# playB.net
KiCad netlist of a schematic drawn in Altium Designer
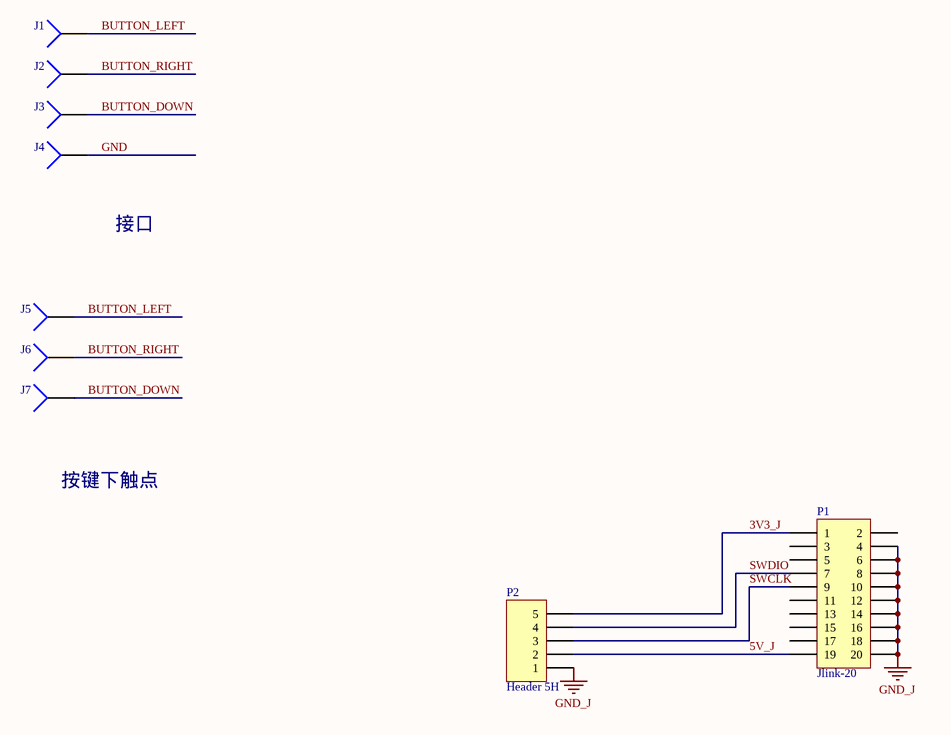
[diagram p0: playB.SchDoc]

(export (version "E")
  (design (tool "Eeschema 10.0.6"))
  (components
    (comp (ref "J1")
      (value "PAD")
      (footprint "LINK_HOLE")
      (description "Socket")
      (fields (field (name "PUBLISHER") "Altium Limited"))
      (libsource (lib "Miscellaneous Connectors") (part "Socket"))
    )
    (comp (ref "J2")
      (value "PAD")
      (footprint "LINK_HOLE")
      (description "Socket")
      (fields (field (name "PUBLISHER") "Altium Limited"))
      (libsource (lib "Miscellaneous Connectors") (part "Socket"))
    )
    (comp (ref "J3")
      (value "PAD")
      (footprint "LINK_HOLE")
      (description "Socket")
      (fields (field (name "PUBLISHER") "Altium Limited"))
      (libsource (lib "Miscellaneous Connectors") (part "Socket"))
    )
    (comp (ref "J4")
      (value "PAD")
      (footprint "LINK_HOLE")
      (description "Socket")
      (fields (field (name "PUBLISHER") "Altium Limited"))
      (libsource (lib "Miscellaneous Connectors") (part "Socket"))
    )
    (comp (ref "J5")
      (value "PAD")
      (footprint "Button_Pad")
      (description "Socket")
      (fields (field (name "PUBLISHER") "Altium Limited"))
      (libsource (lib "Miscellaneous Connectors") (part "Socket"))
    )
    (comp (ref "J6")
      (value "PAD")
      (footprint "Button_Pad")
      (description "Socket")
      (fields (field (name "PUBLISHER") "Altium Limited"))
      (libsource (lib "Miscellaneous Connectors") (part "Socket"))
    )
    (comp (ref "J7")
      (value "PAD")
      (footprint "Button_Pad")
      (description "Socket")
      (fields (field (name "PUBLISHER") "Altium Limited"))
      (libsource (lib "Miscellaneous Connectors") (part "Socket"))
    )
    (comp (ref "P1")
      (value "Jlink-20")
      (footprint "J-LINK")
      (description "Header, 10-Pin, Dual row")
      (fields (field (name "PUBLISHER") "Altium Limited"))
      (libsource (lib "Miscellaneous Connectors") (part "Header 10X2"))
    )
    (comp (ref "P2")
      (value "Header 5H")
      (footprint "connect_5pin")
      (description "Header, 5-Pin, Right Angle")
      (fields (field (name "PUBLISHER") "Altium Limited"))
      (libsource (lib "Miscellaneous Connectors") (part "Header 5H"))
    )
  )
  (nets
    (net (code "1") (name "/3V3_J") (class "Default")
      (node (ref "P1") (pin "1") (pinfunction "1_1") (pintype "passive"))
      (node (ref "P2") (pin "5") (pinfunction "5_5") (pintype "passive"))
    )
    (net (code "2") (name "/5V_J") (class "Default")
      (node (ref "P1") (pin "19") (pinfunction "19_19") (pintype "passive"))
      (node (ref "P2") (pin "2") (pinfunction "2_2") (pintype "passive"))
    )
    (net (code "3") (name "/BUTTON_DOWN") (class "Default")
      (node (ref "J3") (pin "1") (pinfunction "1_1") (pintype "passive"))
      (node (ref "J7") (pin "1") (pinfunction "1_1") (pintype "passive"))
    )
    (net (code "4") (name "/BUTTON_LEFT") (class "Default")
      (node (ref "J1") (pin "1") (pinfunction "1_1") (pintype "passive"))
      (node (ref "J5") (pin "1") (pinfunction "1_1") (pintype "passive"))
    )
    (net (code "5") (name "/BUTTON_RIGHT") (class "Default")
      (node (ref "J2") (pin "1") (pinfunction "1_1") (pintype "passive"))
      (node (ref "J6") (pin "1") (pinfunction "1_1") (pintype "passive"))
    )
    (net (code "6") (name "/GND") (class "Default")
      (node (ref "J4") (pin "1") (pinfunction "1_1") (pintype "passive"))
    )
    (net (code "7") (name "/SWCLK") (class "Default")
      (node (ref "P1") (pin "9") (pinfunction "9_9") (pintype "passive"))
      (node (ref "P2") (pin "3") (pinfunction "3_3") (pintype "passive"))
    )
    (net (code "8") (name "/SWDIO") (class "Default")
      (node (ref "P1") (pin "7") (pinfunction "7_7") (pintype "passive"))
      (node (ref "P2") (pin "4") (pinfunction "4_4") (pintype "passive"))
    )
    (net (code "9") (name "GND_J") (class "Default")
      (node (ref "P1") (pin "10") (pinfunction "10_10") (pintype "passive"))
      (node (ref "P1") (pin "12") (pinfunction "12_12") (pintype "passive"))
      (node (ref "P1") (pin "14") (pinfunction "14_14") (pintype "passive"))
      (node (ref "P1") (pin "16") (pinfunction "16_16") (pintype "passive"))
      (node (ref "P1") (pin "18") (pinfunction "18_18") (pintype "passive"))
      (node (ref "P1") (pin "20") (pinfunction "20_20") (pintype "passive"))
      (node (ref "P1") (pin "4") (pinfunction "4_4") (pintype "passive"))
      (node (ref "P1") (pin "6") (pinfunction "6_6") (pintype "passive"))
      (node (ref "P1") (pin "8") (pinfunction "8_8") (pintype "passive"))
      (node (ref "P2") (pin "1") (pinfunction "1_1") (pintype "passive"))
    )
    (net (code "10") (name "unconnected-(P1-Pad2)") (class "Default")
      (node (ref "P1") (pin "2") (pinfunction "2_2") (pintype "passive"))
    )
    (net (code "11") (name "unconnected-(P1-Pad3)") (class "Default")
      (node (ref "P1") (pin "3") (pinfunction "3_3") (pintype "passive"))
    )
    (net (code "12") (name "unconnected-(P1-Pad5)") (class "Default")
      (node (ref "P1") (pin "5") (pinfunction "5_5") (pintype "passive"))
    )
    (net (code "13") (name "unconnected-(P1-Pad11)") (class "Default")
      (node (ref "P1") (pin "11") (pinfunction "11_11") (pintype "passive"))
    )
    (net (code "14") (name "unconnected-(P1-Pad13)") (class "Default")
      (node (ref "P1") (pin "13") (pinfunction "13_13") (pintype "passive"))
    )
    (net (code "15") (name "unconnected-(P1-Pad15)") (class "Default")
      (node (ref "P1") (pin "15") (pinfunction "15_15") (pintype "passive"))
    )
    (net (code "16") (name "unconnected-(P1-Pad17)") (class "Default")
      (node (ref "P1") (pin "17") (pinfunction "17_17") (pintype "passive"))
    )
  )
)
